# USB.net
KiCad netlist of a schematic drawn in Altium Designer
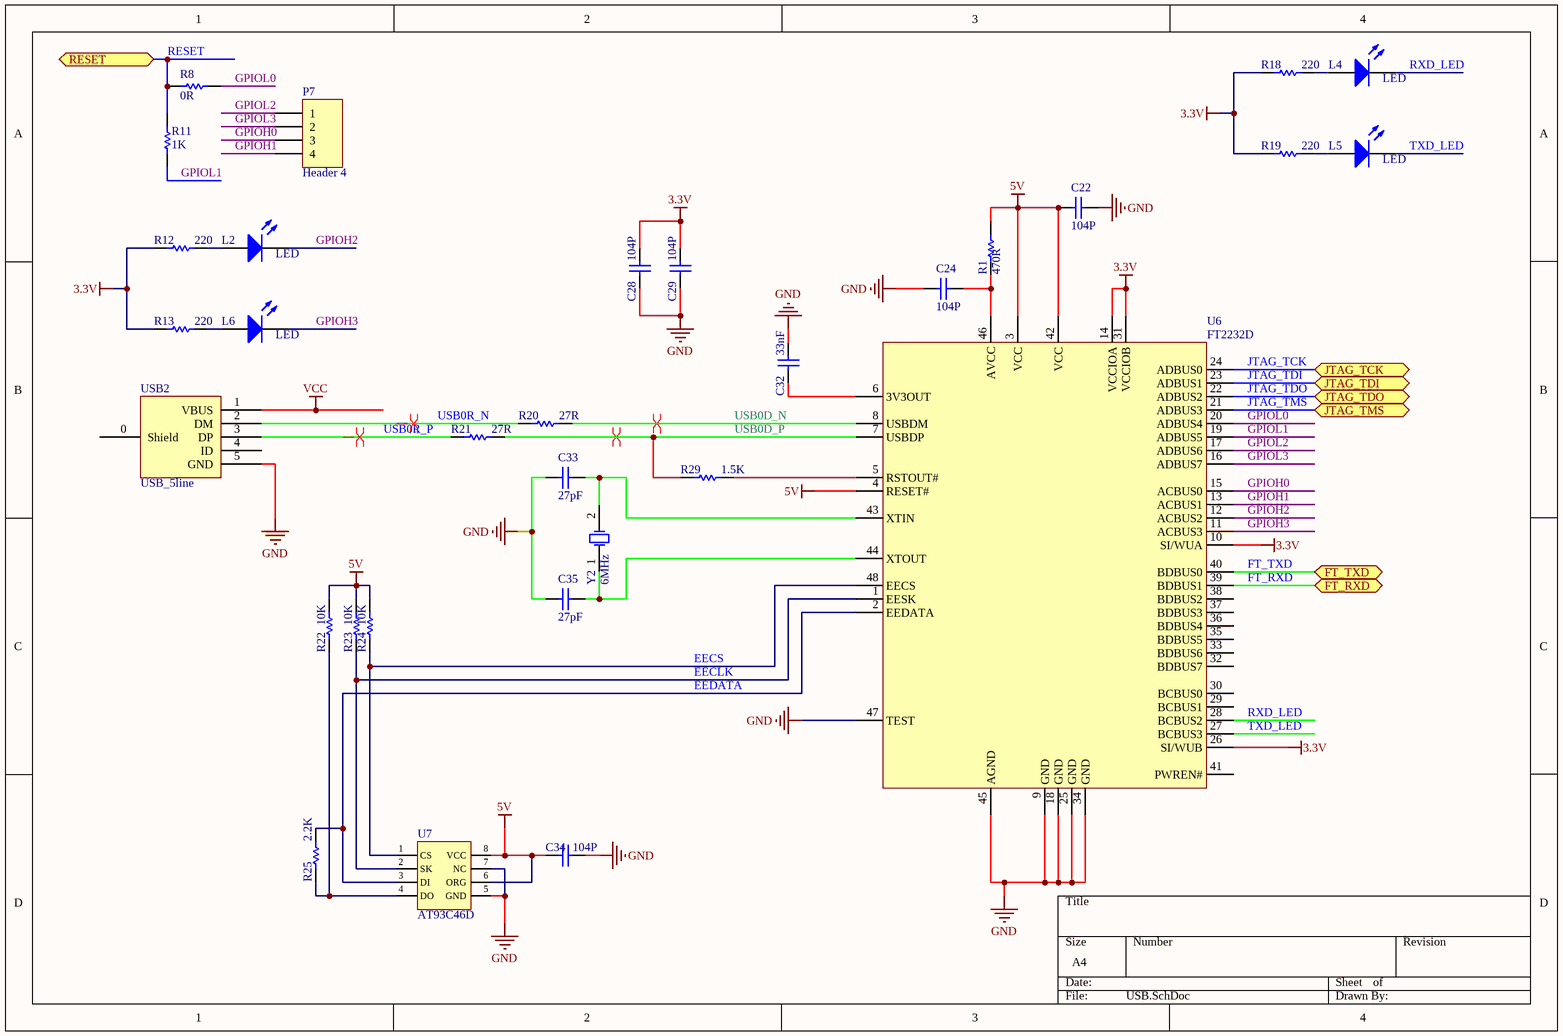
[diagram p0: USB.SchDoc]

(export (version "E")
  (design (tool "Eeschema 10.0.6"))
  (components
    (comp (ref "C22")
      (value "104P")
      (footprint "1608[0603]")
      (description "贴片电容")
      (fields (field (name "Comment") "Cap") (field (name "PUBLISHER") "Altium Limited"))
      (libsource (lib "Sparks") (part "Cap"))
    )
    (comp (ref "C24")
      (value "104P")
      (footprint "1608[0603]")
      (description "贴片电容")
      (fields (field (name "Comment") "Cap") (field (name "PUBLISHER") "Altium Limited"))
      (libsource (lib "Sparks") (part "Cap"))
    )
    (comp (ref "C28")
      (value "104P")
      (footprint "1608[0603]")
      (description "贴片电容")
      (fields (field (name "Comment") "Cap") (field (name "PUBLISHER") "Altium Limited"))
      (libsource (lib "Sparks") (part "Cap"))
    )
    (comp (ref "C29")
      (value "104P")
      (footprint "1608[0603]")
      (description "贴片电容")
      (fields (field (name "Comment") "Cap") (field (name "PUBLISHER") "Altium Limited"))
      (libsource (lib "Sparks") (part "Cap"))
    )
    (comp (ref "C32")
      (value "33nF")
      (footprint "1608[0603]")
      (description "贴片电容")
      (fields (field (name "Comment") "Cap") (field (name "PUBLISHER") "Altium Limited"))
      (libsource (lib "Sparks") (part "Cap"))
    )
    (comp (ref "C33")
      (value "27pF")
      (footprint "1608[0603]")
      (description "贴片电容")
      (fields (field (name "Comment") "Cap") (field (name "PUBLISHER") "Altium Limited"))
      (libsource (lib "Sparks") (part "Cap"))
    )
    (comp (ref "C34")
      (value "104P")
      (footprint "1608[0603]")
      (description "贴片电容")
      (fields (field (name "Comment") "Cap") (field (name "PUBLISHER") "Altium Limited"))
      (libsource (lib "Sparks") (part "Cap"))
    )
    (comp (ref "C35")
      (value "27pF")
      (footprint "1608[0603]")
      (description "贴片电容")
      (fields (field (name "Comment") "Cap") (field (name "PUBLISHER") "Altium Limited"))
      (libsource (lib "Sparks") (part "Cap"))
    )
    (comp (ref "L2") (value "LED") (footprint "1608[0603]") (libsource (lib "Sparks") (part "LED")))
    (comp (ref "L4") (value "LED") (footprint "1608[0603]") (libsource (lib "Sparks") (part "LED")))
    (comp (ref "L5") (value "LED") (footprint "1608[0603]") (libsource (lib "Sparks") (part "LED")))
    (comp (ref "L6") (value "LED") (footprint "1608[0603]") (libsource (lib "Sparks") (part "LED")))
    (comp (ref "P7")
      (value "Header 4")
      (footprint "HDR1X4")
      (description "Header, 4-Pin")
      (fields (field (name "PUBLISHER") "Altium Limited"))
      (libsource (lib "Sparks") (part "Header 4"))
    )
    (comp (ref "R1")
      (value "470R")
      (footprint "1608[0603]")
      (description "贴片电阻")
      (fields (field (name "Comment") "Res") (field (name "PUBLISHER") "Altium Limited"))
      (libsource (lib "Sparks") (part "Res"))
    )
    (comp (ref "R8")
      (value "0R")
      (footprint "1608[0603]")
      (description "贴片电阻")
      (fields (field (name "Comment") "Res") (field (name "PUBLISHER") "Altium Limited"))
      (libsource (lib "Sparks") (part "Res"))
    )
    (comp (ref "R11")
      (value "1K")
      (footprint "1608[0603]")
      (description "贴片电阻")
      (fields (field (name "Comment") "Res") (field (name "PUBLISHER") "Altium Limited"))
      (libsource (lib "Sparks") (part "Res"))
    )
    (comp (ref "R12")
      (value "220")
      (footprint "1608[0603]")
      (description "贴片电阻")
      (fields (field (name "Comment") "Res") (field (name "PUBLISHER") "Altium Limited"))
      (libsource (lib "Sparks") (part "Res"))
    )
    (comp (ref "R13")
      (value "220")
      (footprint "1608[0603]")
      (description "贴片电阻")
      (fields (field (name "Comment") "Res") (field (name "PUBLISHER") "Altium Limited"))
      (libsource (lib "Sparks") (part "Res"))
    )
    (comp (ref "R18")
      (value "220")
      (footprint "1608[0603]")
      (description "贴片电阻")
      (fields (field (name "Comment") "Res") (field (name "PUBLISHER") "Altium Limited"))
      (libsource (lib "Sparks") (part "Res"))
    )
    (comp (ref "R19")
      (value "220")
      (footprint "1608[0603]")
      (description "贴片电阻")
      (fields (field (name "Comment") "Res") (field (name "PUBLISHER") "Altium Limited"))
      (libsource (lib "Sparks") (part "Res"))
    )
    (comp (ref "R20")
      (value "27R")
      (footprint "1608[0603]")
      (description "贴片电阻")
      (fields (field (name "Comment") "Res") (field (name "PUBLISHER") "Altium Limited"))
      (libsource (lib "Sparks") (part "Res"))
    )
    (comp (ref "R21")
      (value "27R")
      (footprint "1608[0603]")
      (description "贴片电阻")
      (fields (field (name "Comment") "Res") (field (name "PUBLISHER") "Altium Limited"))
      (libsource (lib "Sparks") (part "Res"))
    )
    (comp (ref "R22")
      (value "10K")
      (footprint "1608[0603]")
      (description "贴片电阻")
      (fields (field (name "Comment") "Res") (field (name "PUBLISHER") "Altium Limited"))
      (libsource (lib "Sparks") (part "Res"))
    )
    (comp (ref "R23")
      (value "10K")
      (footprint "1608[0603]")
      (description "贴片电阻")
      (fields (field (name "Comment") "Res") (field (name "PUBLISHER") "Altium Limited"))
      (libsource (lib "Sparks") (part "Res"))
    )
    (comp (ref "R24")
      (value "10K")
      (footprint "1608[0603]")
      (description "贴片电阻")
      (fields (field (name "Comment") "Res") (field (name "PUBLISHER") "Altium Limited"))
      (libsource (lib "Sparks") (part "Res"))
    )
    (comp (ref "R25")
      (value "2.2K")
      (footprint "1608[0603]")
      (description "贴片电阻")
      (fields (field (name "Comment") "Res") (field (name "PUBLISHER") "Altium Limited"))
      (libsource (lib "Sparks") (part "Res"))
    )
    (comp (ref "R29")
      (value "1.5K")
      (footprint "1608[0603]")
      (description "贴片电阻")
      (fields (field (name "Comment") "Res") (field (name "PUBLISHER") "Altium Limited"))
      (libsource (lib "Sparks") (part "Res"))
    )
    (comp (ref "U6")
      (value "FT2232D")
      (footprint "TSQFP50P900X900X160-48N")
      (libsource (lib "2号库") (part "FT2232D"))
    )
    (comp (ref "U7")
      (value "AT93C46D")
      (footprint "TSOP65P640X120-8N-AT93C46D")
      (libsource (lib "2号库") (part "AT93C46D"))
    )
    (comp (ref "USB2")
      (value "USB_5line")
      (footprint "USB-MICRO-5P-2F")
      (libsource (lib "2号库") (part "USB_5line"))
    )
    (comp (ref "Y2")
      (value "6MHz")
      (footprint "XTAL-RAD-0.2")
      (description "晶体振荡器")
      (fields (field (name "PUBLISHER") "Altium Limited"))
      (libsource (lib "Sparks") (part "XTAL"))
    )
  )
  (nets
    (net (code "1") (name "/EECLK") (class "Default")
      (node (ref "R23") (pin "2") (pinfunction "2_2") (pintype "passive"))
      (node (ref "U6") (pin "1") (pinfunction "EESK_1") (pintype "passive"))
      (node (ref "U7") (pin "2") (pinfunction "SK_2") (pintype "passive"))
    )
    (net (code "2") (name "/EECS") (class "Default")
      (node (ref "R24") (pin "2") (pinfunction "2_2") (pintype "passive"))
      (node (ref "U6") (pin "48") (pinfunction "EECS_48") (pintype "passive"))
      (node (ref "U7") (pin "1") (pinfunction "CS_1") (pintype "passive"))
    )
    (net (code "3") (name "/EEDATA") (class "Default")
      (node (ref "R25") (pin "1") (pinfunction "1_1") (pintype "passive"))
      (node (ref "U6") (pin "2") (pinfunction "EEDATA_2") (pintype "passive"))
      (node (ref "U7") (pin "3") (pinfunction "DI_3") (pintype "passive"))
    )
    (net (code "4") (name "/FT_RXD") (class "Default")
      (node (ref "U6") (pin "39") (pinfunction "BDBUS1_39") (pintype "passive"))
    )
    (net (code "5") (name "/FT_TXD") (class "Default")
      (node (ref "U6") (pin "40") (pinfunction "BDBUS0_40") (pintype "passive"))
    )
    (net (code "6") (name "/GPIOH0") (class "Default")
      (node (ref "P7") (pin "3") (pinfunction "3_3") (pintype "passive"))
      (node (ref "U6") (pin "15") (pinfunction "ACBUS0_15") (pintype "passive"))
    )
    (net (code "7") (name "/GPIOH1") (class "Default")
      (node (ref "P7") (pin "4") (pinfunction "4_4") (pintype "passive"))
      (node (ref "U6") (pin "13") (pinfunction "ACBUS1_13") (pintype "passive"))
    )
    (net (code "8") (name "/GPIOH2") (class "Default")
      (node (ref "L2") (pin "2") (pinfunction "K_2") (pintype "passive"))
      (node (ref "U6") (pin "12") (pinfunction "ACBUS2_12") (pintype "passive"))
    )
    (net (code "9") (name "/GPIOH3") (class "Default")
      (node (ref "L6") (pin "2") (pinfunction "K_2") (pintype "passive"))
      (node (ref "U6") (pin "11") (pinfunction "ACBUS3_11") (pintype "passive"))
    )
    (net (code "10") (name "/GPIOL0") (class "Default")
      (node (ref "R8") (pin "2") (pinfunction "2_2") (pintype "passive"))
      (node (ref "U6") (pin "20") (pinfunction "ADBUS4_20") (pintype "passive"))
    )
    (net (code "11") (name "/GPIOL1") (class "Default")
      (node (ref "R11") (pin "2") (pinfunction "2_2") (pintype "passive"))
      (node (ref "U6") (pin "19") (pinfunction "ADBUS5_19") (pintype "passive"))
    )
    (net (code "12") (name "/GPIOL2") (class "Default")
      (node (ref "P7") (pin "1") (pinfunction "1_1") (pintype "passive"))
      (node (ref "U6") (pin "17") (pinfunction "ADBUS6_17") (pintype "passive"))
    )
    (net (code "13") (name "/GPIOL3") (class "Default")
      (node (ref "P7") (pin "2") (pinfunction "2_2") (pintype "passive"))
      (node (ref "U6") (pin "16") (pinfunction "ADBUS7_16") (pintype "passive"))
    )
    (net (code "14") (name "/JTAG_TCK") (class "Default")
      (node (ref "U6") (pin "24") (pinfunction "ADBUS0_24") (pintype "passive"))
    )
    (net (code "15") (name "/JTAG_TDI") (class "Default")
      (node (ref "U6") (pin "23") (pinfunction "ADBUS1_23") (pintype "passive"))
    )
    (net (code "16") (name "/JTAG_TDO") (class "Default")
      (node (ref "U6") (pin "22") (pinfunction "ADBUS2_22") (pintype "passive"))
    )
    (net (code "17") (name "/JTAG_TMS") (class "Default")
      (node (ref "U6") (pin "21") (pinfunction "ADBUS3_21") (pintype "passive"))
    )
    (net (code "18") (name "/RESET") (class "Default")
      (node (ref "R11") (pin "1") (pinfunction "1_1") (pintype "passive"))
      (node (ref "R8") (pin "1") (pinfunction "1_1") (pintype "passive"))
    )
    (net (code "19") (name "/RXD_LED") (class "Default")
      (node (ref "L4") (pin "2") (pinfunction "K_2") (pintype "passive"))
      (node (ref "U6") (pin "28") (pinfunction "BCBUS2_28") (pintype "passive"))
    )
    (net (code "20") (name "/TXD_LED") (class "Default")
      (node (ref "L5") (pin "2") (pinfunction "K_2") (pintype "passive"))
      (node (ref "U6") (pin "27") (pinfunction "BCBUS3_27") (pintype "passive"))
    )
    (net (code "21") (name "/USB0D_N") (class "Default")
      (node (ref "R20") (pin "2") (pinfunction "2_2") (pintype "passive"))
      (node (ref "U6") (pin "8") (pinfunction "USBDM_8") (pintype "passive"))
    )
    (net (code "22") (name "/USB0D_P") (class "Default")
      (node (ref "R21") (pin "2") (pinfunction "2_2") (pintype "passive"))
      (node (ref "R29") (pin "1") (pinfunction "1_1") (pintype "passive"))
      (node (ref "U6") (pin "7") (pinfunction "USBDP_7") (pintype "passive"))
    )
    (net (code "23") (name "/USB0R_N") (class "Default")
      (node (ref "R20") (pin "1") (pinfunction "1_1") (pintype "passive"))
      (node (ref "USB2") (pin "2") (pinfunction "DM_2") (pintype "passive"))
    )
    (net (code "24") (name "/USB0R_P") (class "Default")
      (node (ref "R21") (pin "1") (pinfunction "1_1") (pintype "passive"))
      (node (ref "USB2") (pin "3") (pinfunction "DP_3") (pintype "passive"))
    )
    (net (code "25") (name "3.3V") (class "Default")
      (node (ref "C28") (pin "2") (pinfunction "2_2") (pintype "passive"))
      (node (ref "C29") (pin "2") (pinfunction "2_2") (pintype "passive"))
      (node (ref "R12") (pin "2") (pinfunction "2_2") (pintype "passive"))
      (node (ref "R13") (pin "2") (pinfunction "2_2") (pintype "passive"))
      (node (ref "R18") (pin "2") (pinfunction "2_2") (pintype "passive"))
      (node (ref "R19") (pin "2") (pinfunction "2_2") (pintype "passive"))
      (node (ref "U6") (pin "10") (pinfunction "SI/WUA_10") (pintype "passive"))
      (node (ref "U6") (pin "14") (pinfunction "VCCIOA_14") (pintype "passive"))
      (node (ref "U6") (pin "26") (pinfunction "SI/WUB_26") (pintype "passive"))
      (node (ref "U6") (pin "31") (pinfunction "VCCIOB_31") (pintype "passive"))
    )
    (net (code "26") (name "5V") (class "Default")
      (node (ref "C22") (pin "2") (pinfunction "2_2") (pintype "passive"))
      (node (ref "C34") (pin "2") (pinfunction "2_2") (pintype "passive"))
      (node (ref "R1") (pin "1") (pinfunction "1_1") (pintype "passive"))
      (node (ref "R22") (pin "1") (pinfunction "1_1") (pintype "passive"))
      (node (ref "R23") (pin "1") (pinfunction "1_1") (pintype "passive"))
      (node (ref "R24") (pin "1") (pinfunction "1_1") (pintype "passive"))
      (node (ref "U6") (pin "3") (pinfunction "VCC_3") (pintype "passive"))
      (node (ref "U6") (pin "4") (pinfunction "RESET#_4") (pintype "passive"))
      (node (ref "U6") (pin "42") (pinfunction "VCC_42") (pintype "passive"))
      (node (ref "U7") (pin "6") (pinfunction "ORG_6") (pintype "passive"))
      (node (ref "U7") (pin "8") (pinfunction "VCC_8") (pintype "passive"))
    )
    (net (code "27") (name "GND") (class "Default")
      (node (ref "C22") (pin "1") (pinfunction "1_1") (pintype "passive"))
      (node (ref "C24") (pin "2") (pinfunction "2_2") (pintype "passive"))
      (node (ref "C28") (pin "1") (pinfunction "1_1") (pintype "passive"))
      (node (ref "C29") (pin "1") (pinfunction "1_1") (pintype "passive"))
      (node (ref "C32") (pin "2") (pinfunction "2_2") (pintype "passive"))
      (node (ref "C33") (pin "1") (pinfunction "1_1") (pintype "passive"))
      (node (ref "C34") (pin "1") (pinfunction "1_1") (pintype "passive"))
      (node (ref "C35") (pin "2") (pinfunction "2_2") (pintype "passive"))
      (node (ref "U6") (pin "18") (pinfunction "GND_18") (pintype "passive"))
      (node (ref "U6") (pin "25") (pinfunction "GND_25") (pintype "passive"))
      (node (ref "U6") (pin "34") (pinfunction "GND_34") (pintype "passive"))
      (node (ref "U6") (pin "45") (pinfunction "AGND_45") (pintype "passive"))
      (node (ref "U6") (pin "47") (pinfunction "TEST_47") (pintype "passive"))
      (node (ref "U6") (pin "9") (pinfunction "GND_9") (pintype "passive"))
      (node (ref "U7") (pin "5") (pinfunction "GND_5") (pintype "passive"))
      (node (ref "U7") (pin "7") (pinfunction "NC_7") (pintype "passive"))
      (node (ref "USB2") (pin "5") (pinfunction "GND_5") (pintype "passive"))
    )
    (net (code "28") (name "Net-(L2-A)") (class "Default")
      (node (ref "L2") (pin "1") (pinfunction "A_1") (pintype "passive"))
      (node (ref "R12") (pin "1") (pinfunction "1_1") (pintype "passive"))
    )
    (net (code "29") (name "Net-(L4-A)") (class "Default")
      (node (ref "L4") (pin "1") (pinfunction "A_1") (pintype "passive"))
      (node (ref "R18") (pin "1") (pinfunction "1_1") (pintype "passive"))
    )
    (net (code "30") (name "Net-(L5-A)") (class "Default")
      (node (ref "L5") (pin "1") (pinfunction "A_1") (pintype "passive"))
      (node (ref "R19") (pin "1") (pinfunction "1_1") (pintype "passive"))
    )
    (net (code "31") (name "Net-(L6-A)") (class "Default")
      (node (ref "L6") (pin "1") (pinfunction "A_1") (pintype "passive"))
      (node (ref "R13") (pin "1") (pinfunction "1_1") (pintype "passive"))
    )
    (net (code "32") (name "Net-(U6-3V3OUT)") (class "Default")
      (node (ref "C32") (pin "1") (pinfunction "1_1") (pintype "passive"))
      (node (ref "U6") (pin "6") (pinfunction "3V3OUT_6") (pintype "passive"))
    )
    (net (code "33") (name "Net-(U6-AVCC)") (class "Default")
      (node (ref "C24") (pin "1") (pinfunction "1_1") (pintype "passive"))
      (node (ref "R1") (pin "2") (pinfunction "2_2") (pintype "passive"))
      (node (ref "U6") (pin "46") (pinfunction "AVCC_46") (pintype "passive"))
    )
    (net (code "34") (name "Net-(U6-RSTOUT#)") (class "Default")
      (node (ref "R29") (pin "2") (pinfunction "2_2") (pintype "passive"))
      (node (ref "U6") (pin "5") (pinfunction "RSTOUT#_5") (pintype "passive"))
    )
    (net (code "35") (name "Net-(U6-XTIN)") (class "Default")
      (node (ref "C33") (pin "2") (pinfunction "2_2") (pintype "passive"))
      (node (ref "U6") (pin "43") (pinfunction "XTIN_43") (pintype "passive"))
      (node (ref "Y2") (pin "2") (pinfunction "OSC2_2") (pintype "passive"))
    )
    (net (code "36") (name "Net-(U6-XTOUT)") (class "Default")
      (node (ref "C35") (pin "1") (pinfunction "1_1") (pintype "passive"))
      (node (ref "U6") (pin "44") (pinfunction "XTOUT_44") (pintype "passive"))
      (node (ref "Y2") (pin "1") (pinfunction "OSC1_1") (pintype "passive"))
    )
    (net (code "37") (name "Net-(U7-DO)") (class "Default")
      (node (ref "R22") (pin "2") (pinfunction "2_2") (pintype "passive"))
      (node (ref "R25") (pin "2") (pinfunction "2_2") (pintype "passive"))
      (node (ref "U7") (pin "4") (pinfunction "DO_4") (pintype "passive"))
    )
    (net (code "38") (name "VCC") (class "Default")
      (node (ref "USB2") (pin "1") (pinfunction "VBUS_1") (pintype "passive"))
    )
    (net (code "39") (name "unconnected-(U6-BCBUS0-Pad30)") (class "Default")
      (node (ref "U6") (pin "30") (pinfunction "BCBUS0_30") (pintype "passive"))
    )
    (net (code "40") (name "unconnected-(U6-BCBUS1-Pad29)") (class "Default")
      (node (ref "U6") (pin "29") (pinfunction "BCBUS1_29") (pintype "passive"))
    )
    (net (code "41") (name "unconnected-(U6-BDBUS2-Pad38)") (class "Default")
      (node (ref "U6") (pin "38") (pinfunction "BDBUS2_38") (pintype "passive"))
    )
    (net (code "42") (name "unconnected-(U6-BDBUS3-Pad37)") (class "Default")
      (node (ref "U6") (pin "37") (pinfunction "BDBUS3_37") (pintype "passive"))
    )
    (net (code "43") (name "unconnected-(U6-BDBUS4-Pad36)") (class "Default")
      (node (ref "U6") (pin "36") (pinfunction "BDBUS4_36") (pintype "passive"))
    )
    (net (code "44") (name "unconnected-(U6-BDBUS5-Pad35)") (class "Default")
      (node (ref "U6") (pin "35") (pinfunction "BDBUS5_35") (pintype "passive"))
    )
    (net (code "45") (name "unconnected-(U6-BDBUS6-Pad33)") (class "Default")
      (node (ref "U6") (pin "33") (pinfunction "BDBUS6_33") (pintype "passive"))
    )
    (net (code "46") (name "unconnected-(U6-BDBUS7-Pad32)") (class "Default")
      (node (ref "U6") (pin "32") (pinfunction "BDBUS7_32") (pintype "passive"))
    )
    (net (code "47") (name "unconnected-(U6-PWREN#-Pad41)") (class "Default")
      (node (ref "U6") (pin "41") (pinfunction "PWREN#_41") (pintype "passive"))
    )
    (net (code "48") (name "unconnected-(USB2-ID-Pad4)") (class "Default")
      (node (ref "USB2") (pin "4") (pinfunction "ID_4") (pintype "passive"))
    )
    (net (code "49") (name "unconnected-(USB2-Shield-Pad0)") (class "Default")
      (node (ref "USB2") (pin "0") (pinfunction "Shield_0") (pintype "passive"))
    )
  )
)
